# ACME.net
KiCad netlist of a schematic drawn in EAGLE
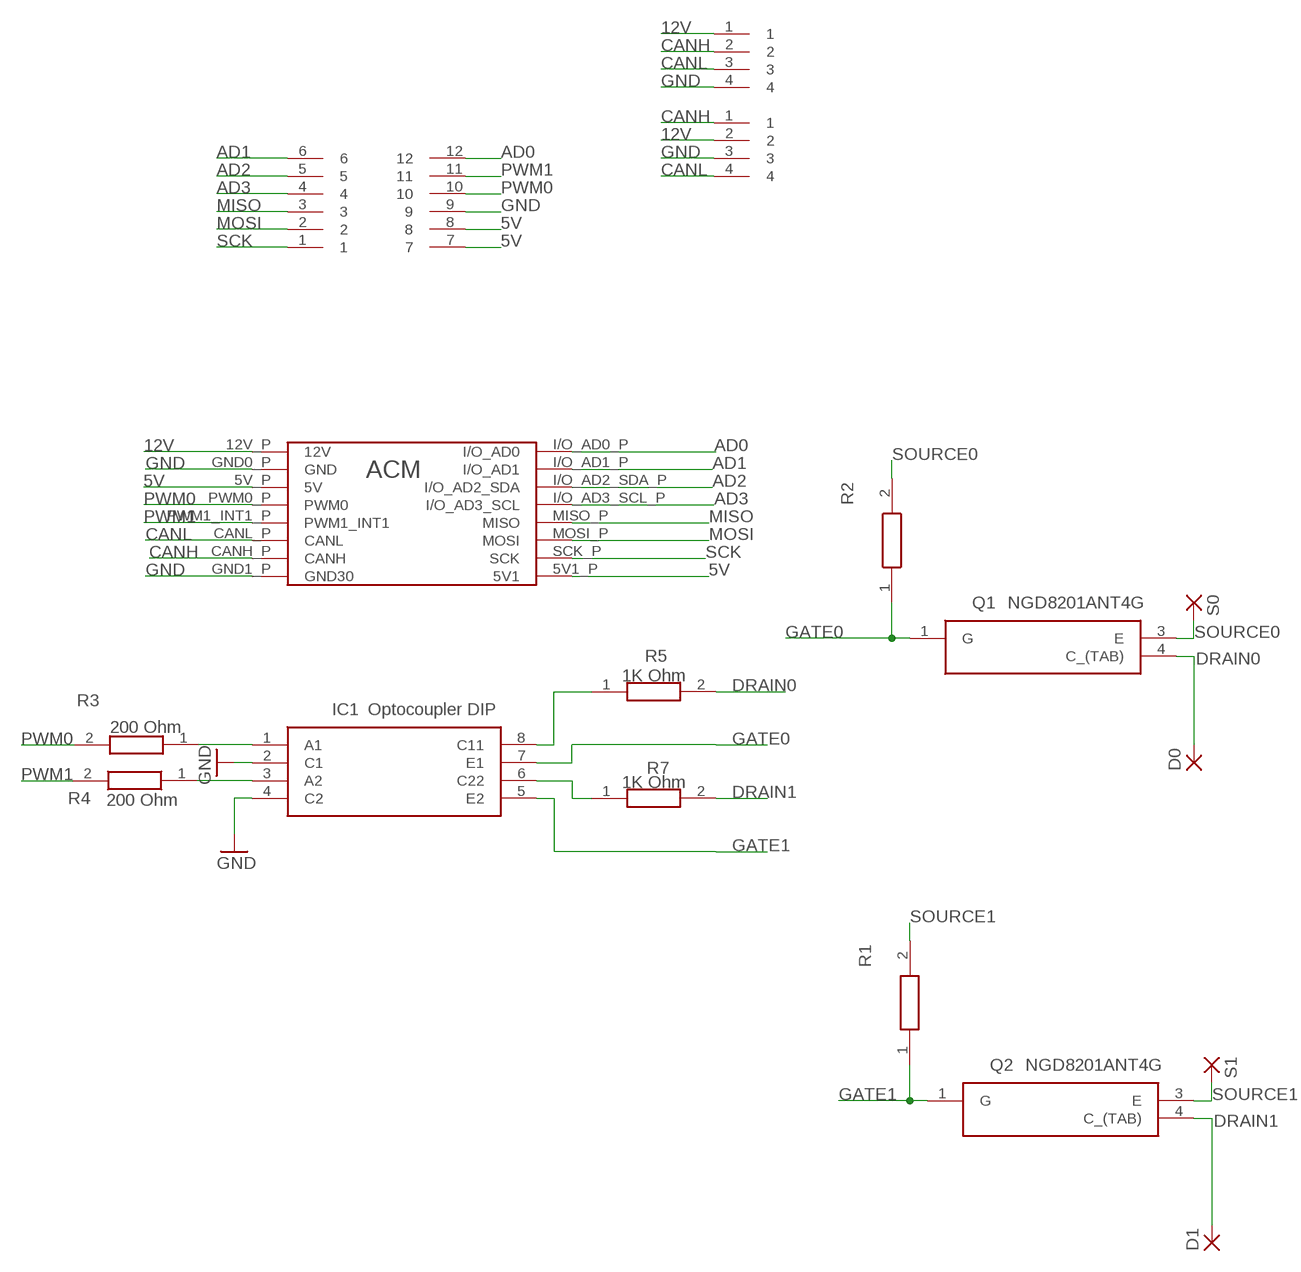
[diagram p0: schematic, sheet 1]

(export (version "E")
  (design (tool "Eeschema 10.0.6"))
  (components
    (comp (ref "D0")
      (value "WIREPADSMD5-2,5")
      (footprint "eagle-import:5-2,5")
      (libsource (lib "eagle-import") (part "WIREPADSMD5-2,5"))
    )
    (comp (ref "D1")
      (value "WIREPADSMD5-2,5")
      (footprint "eagle-import:5-2,5")
      (libsource (lib "eagle-import") (part "WIREPADSMD5-2,5"))
    )
    (comp (ref "IC1")
      (value "Optocoupler DIP")
      (footprint "eagle-import:DIP762W60P254L966H485Q8N")
      (fields
        (field (name "MANUFACTURER_PART_NUMBER") "TLP350(F)")
        (field (name "MOUSER_PART_NUMBER") "757-TLP350(F)")
        (field (name "RS_PART_NUMBER") "0186022P")
      )
      (libsource (lib "eagle-import") (part "TLP350(F)"))
    )
    (comp (ref "Q1")
      (value "NGD8201ANT4G")
      (footprint "eagle-import:TO229P990X238-4N")
      (fields (field (name "MOUSER_PART_NUMBER") "7470901"))
      (libsource (lib "eagle-import") (part "NGD8201ANT4G"))
    )
    (comp (ref "Q2")
      (value "NGD8201ANT4G")
      (footprint "eagle-import:TO229P990X238-4N")
      (fields (field (name "MOUSER_PART_NUMBER") "7470901"))
      (libsource (lib "eagle-import") (part "NGD8201ANT4G"))
    )
    (comp (ref "R1")
      (value "ERA-3AEB2262V")
      (footprint "eagle-import:RESC1608X55N")
      (fields (field (name "MOUSER_PART_NUMBER") "667-ERA-3AEB2262V"))
      (libsource (lib "eagle-import") (part "ERA-3AEB2262V"))
    )
    (comp (ref "R2")
      (value "ERA-3AEB2262V")
      (footprint "eagle-import:RESC1608X55N")
      (fields (field (name "MOUSER_PART_NUMBER") "667-ERA-3AEB2262V"))
      (libsource (lib "eagle-import") (part "ERA-3AEB2262V"))
    )
    (comp (ref "R3")
      (value "200 Ohm")
      (footprint "eagle-import:RESC1608X55N")
      (fields
        (field (name "MANUFACTURER_PART_NUMBER") "ERA-3AEB2262V")
        (field (name "MOUSER_PART_NUMBER") "667-ERA-3AEB2262V")
      )
      (libsource (lib "eagle-import") (part "ERA-3AEB2262V"))
    )
    (comp (ref "R4")
      (value "200 Ohm")
      (footprint "eagle-import:RESC1608X55N")
      (fields
        (field (name "MANUFACTURER_PART_NUMBER") "ERA-3AEB2262V")
        (field (name "MOUSER_PART_NUMBER") "667-ERA-3AEB2262V")
      )
      (libsource (lib "eagle-import") (part "ERA-3AEB2262V"))
    )
    (comp (ref "R5")
      (value "1K Ohm")
      (footprint "eagle-import:RESC1608X55N")
      (fields
        (field (name "MANUFACTURER_PART_NUMBER") "ERA-3AEB2262V")
        (field (name "MOUSER_PART_NUMBER") "667-ERA-3AEB2262V")
      )
      (libsource (lib "eagle-import") (part "ERA-3AEB2262V"))
    )
    (comp (ref "R7")
      (value "1K Ohm")
      (footprint "eagle-import:RESC1608X55N")
      (fields
        (field (name "MANUFACTURER_PART_NUMBER") "ERA-3AEB2262V")
        (field (name "MOUSER_PART_NUMBER") "667-ERA-3AEB2262V")
      )
      (libsource (lib "eagle-import") (part "ERA-3AEB2262V"))
    )
    (comp (ref "S0")
      (value "WIREPADSMD5-2,5")
      (footprint "eagle-import:5-2,5")
      (libsource (lib "eagle-import") (part "WIREPADSMD5-2,5"))
    )
    (comp (ref "S1")
      (value "WIREPADSMD5-2,5")
      (footprint "eagle-import:5-2,5")
      (libsource (lib "eagle-import") (part "WIREPADSMD5-2,5"))
    )
    (comp (ref "U$1")
      (value "ACM_CASTELLATED")
      (footprint "eagle-import:ACM_CAS_FP")
      (libsource (lib "eagle-import") (part "ACM_CASTELLATED"))
    )
    (comp (ref "U$2")
      (value "16P_CONNECTOR")
      (footprint "eagle-import:16P_CONNECTOR_FP")
      (libsource (lib "eagle-import") (part "16P_CONNECTOR"))
    )
    (comp (ref "U$3")
      (value "16P_CONNECTOR")
      (footprint "eagle-import:16P_CONNECTOR_FP")
      (libsource (lib "eagle-import") (part "4P_Connector holes_16P_CONNECTOR"))
    )
    (comp (ref "U$4")
      (value "16P_CONNECTOR")
      (footprint "eagle-import:16P_CONNECTOR_FP")
      (libsource (lib "eagle-import") (part "4P_Connector holes_16P_CONNECTOR"))
    )
  )
  (nets
    (net (code "1") (name "/5V") (class "Default")
      (node (ref "U$1") (pin "5V1_P") (pinfunction "5V1_5V1_P") (pintype "bidirectional"))
      (node (ref "U$1") (pin "5V_P") (pinfunction "5V_5V_P") (pintype "bidirectional"))
      (node (ref "U$2") (pin "7") (pinfunction "7_7") (pintype "bidirectional"))
      (node (ref "U$2") (pin "8") (pinfunction "8_8") (pintype "bidirectional"))
    )
    (net (code "2") (name "/12V") (class "Default")
      (node (ref "U$1") (pin "12V_P") (pinfunction "12V_12V_P") (pintype "bidirectional"))
      (node (ref "U$3") (pin "1") (pinfunction "1_1") (pintype "bidirectional"))
      (node (ref "U$4") (pin "2") (pinfunction "2_2") (pintype "bidirectional"))
    )
    (net (code "3") (name "/AD0") (class "Default")
      (node (ref "U$1") (pin "I/O_AD0_P") (pinfunction "I/O_AD0_I/O_AD0_P") (pintype "bidirectional"))
      (node (ref "U$2") (pin "12") (pinfunction "12_12") (pintype "bidirectional"))
    )
    (net (code "4") (name "/AD1") (class "Default")
      (node (ref "U$1") (pin "I/O_AD1_P") (pinfunction "I/O_AD1_I/O_AD1_P") (pintype "bidirectional"))
      (node (ref "U$2") (pin "6") (pinfunction "6_6") (pintype "bidirectional"))
    )
    (net (code "5") (name "/AD2") (class "Default")
      (node (ref "U$1") (pin "I/O_AD2_SDA_P") (pinfunction "I/O_AD2_SDA_I/O_AD2_SDA_P") (pintype "bidirectional"))
      (node (ref "U$2") (pin "5") (pinfunction "5_5") (pintype "bidirectional"))
    )
    (net (code "6") (name "/AD3") (class "Default")
      (node (ref "U$1") (pin "I/O_AD3_SCL_P") (pinfunction "I/O_AD3_SCL_I/O_AD3_SCL_P") (pintype "bidirectional"))
      (node (ref "U$2") (pin "4") (pinfunction "4_4") (pintype "bidirectional"))
    )
    (net (code "7") (name "/CANH") (class "Default")
      (node (ref "U$1") (pin "CANH_P") (pinfunction "CANH_CANH_P") (pintype "bidirectional"))
      (node (ref "U$3") (pin "2") (pinfunction "2_2") (pintype "bidirectional"))
      (node (ref "U$4") (pin "1") (pinfunction "1_1") (pintype "bidirectional"))
    )
    (net (code "8") (name "/CANL") (class "Default")
      (node (ref "U$1") (pin "CANL_P") (pinfunction "CANL_CANL_P") (pintype "bidirectional"))
      (node (ref "U$3") (pin "3") (pinfunction "3_3") (pintype "bidirectional"))
      (node (ref "U$4") (pin "4") (pinfunction "4_4") (pintype "bidirectional"))
    )
    (net (code "9") (name "/DRAIN0") (class "Default")
      (node (ref "D0") (pin "1") (pinfunction "P_1") (pintype "passive"))
      (node (ref "Q1") (pin "4") (pinfunction "C_(TAB)_4") (pintype "bidirectional"))
      (node (ref "R5") (pin "2") (pinfunction "2_2") (pintype "bidirectional"))
    )
    (net (code "10") (name "/DRAIN1") (class "Default")
      (node (ref "D1") (pin "1") (pinfunction "P_1") (pintype "passive"))
      (node (ref "Q2") (pin "4") (pinfunction "C_(TAB)_4") (pintype "bidirectional"))
      (node (ref "R7") (pin "2") (pinfunction "2_2") (pintype "bidirectional"))
    )
    (net (code "11") (name "/GATE0") (class "Default")
      (node (ref "IC1") (pin "7") (pinfunction "E1_7") (pintype "bidirectional"))
      (node (ref "Q1") (pin "1") (pinfunction "G_1") (pintype "bidirectional"))
      (node (ref "R2") (pin "1") (pinfunction "1_1") (pintype "bidirectional"))
    )
    (net (code "12") (name "/GATE1") (class "Default")
      (node (ref "IC1") (pin "5") (pinfunction "E2_5") (pintype "bidirectional"))
      (node (ref "Q2") (pin "1") (pinfunction "G_1") (pintype "bidirectional"))
      (node (ref "R1") (pin "1") (pinfunction "1_1") (pintype "bidirectional"))
    )
    (net (code "13") (name "/MISO") (class "Default")
      (node (ref "U$1") (pin "MISO_P") (pinfunction "MISO_MISO_P") (pintype "bidirectional"))
      (node (ref "U$2") (pin "3") (pinfunction "3_3") (pintype "bidirectional"))
    )
    (net (code "14") (name "/MOSI") (class "Default")
      (node (ref "U$1") (pin "MOSI_P") (pinfunction "MOSI_MOSI_P") (pintype "bidirectional"))
      (node (ref "U$2") (pin "2") (pinfunction "2_2") (pintype "bidirectional"))
    )
    (net (code "15") (name "/PWM0") (class "Default")
      (node (ref "R3") (pin "2") (pinfunction "2_2") (pintype "bidirectional"))
      (node (ref "U$1") (pin "PWM0_P") (pinfunction "PWM0_PWM0_P") (pintype "bidirectional"))
      (node (ref "U$2") (pin "10") (pinfunction "10_10") (pintype "bidirectional"))
    )
    (net (code "16") (name "/PWM1") (class "Default")
      (node (ref "R4") (pin "2") (pinfunction "2_2") (pintype "bidirectional"))
      (node (ref "U$1") (pin "PWM1_INT1_P") (pinfunction "PWM1_INT1_PWM1_INT1_P") (pintype "bidirectional"))
      (node (ref "U$2") (pin "11") (pinfunction "11_11") (pintype "bidirectional"))
    )
    (net (code "17") (name "/SCK") (class "Default")
      (node (ref "U$1") (pin "SCK_P") (pinfunction "SCK_SCK_P") (pintype "bidirectional"))
      (node (ref "U$2") (pin "1") (pinfunction "1_1") (pintype "bidirectional"))
    )
    (net (code "18") (name "/SOURCE0") (class "Default")
      (node (ref "Q1") (pin "3") (pinfunction "E_3") (pintype "bidirectional"))
      (node (ref "R2") (pin "2") (pinfunction "2_2") (pintype "bidirectional"))
      (node (ref "S0") (pin "1") (pinfunction "P_1") (pintype "passive"))
    )
    (net (code "19") (name "/SOURCE1") (class "Default")
      (node (ref "Q2") (pin "3") (pinfunction "E_3") (pintype "bidirectional"))
      (node (ref "R1") (pin "2") (pinfunction "2_2") (pintype "bidirectional"))
      (node (ref "S1") (pin "1") (pinfunction "P_1") (pintype "passive"))
    )
    (net (code "20") (name "GND") (class "Default")
      (node (ref "IC1") (pin "2") (pinfunction "C1_2") (pintype "bidirectional"))
      (node (ref "IC1") (pin "4") (pinfunction "C2_4") (pintype "bidirectional"))
      (node (ref "U$1") (pin "GND0_P") (pinfunction "GND_GND0_P") (pintype "bidirectional"))
      (node (ref "U$1") (pin "GND1_P") (pinfunction "GND30_GND1_P") (pintype "bidirectional"))
      (node (ref "U$2") (pin "9") (pinfunction "9_9") (pintype "bidirectional"))
      (node (ref "U$3") (pin "4") (pinfunction "4_4") (pintype "bidirectional"))
      (node (ref "U$4") (pin "3") (pinfunction "3_3") (pintype "bidirectional"))
    )
    (net (code "21") (name "Net-(IC1-A1)") (class "Default")
      (node (ref "IC1") (pin "1") (pinfunction "A1_1") (pintype "bidirectional"))
      (node (ref "R3") (pin "1") (pinfunction "1_1") (pintype "bidirectional"))
    )
    (net (code "22") (name "Net-(IC1-A2)") (class "Default")
      (node (ref "IC1") (pin "3") (pinfunction "A2_3") (pintype "bidirectional"))
      (node (ref "R4") (pin "1") (pinfunction "1_1") (pintype "bidirectional"))
    )
    (net (code "23") (name "Net-(IC1-C11)") (class "Default")
      (node (ref "IC1") (pin "8") (pinfunction "C11_8") (pintype "bidirectional"))
      (node (ref "R5") (pin "1") (pinfunction "1_1") (pintype "bidirectional"))
    )
    (net (code "24") (name "Net-(IC1-C22)") (class "Default")
      (node (ref "IC1") (pin "6") (pinfunction "C22_6") (pintype "bidirectional"))
      (node (ref "R7") (pin "1") (pinfunction "1_1") (pintype "bidirectional"))
    )
  )
)
